# accero_humid_rtc.net
KiCad netlist of a schematic drawn in Altium Designer
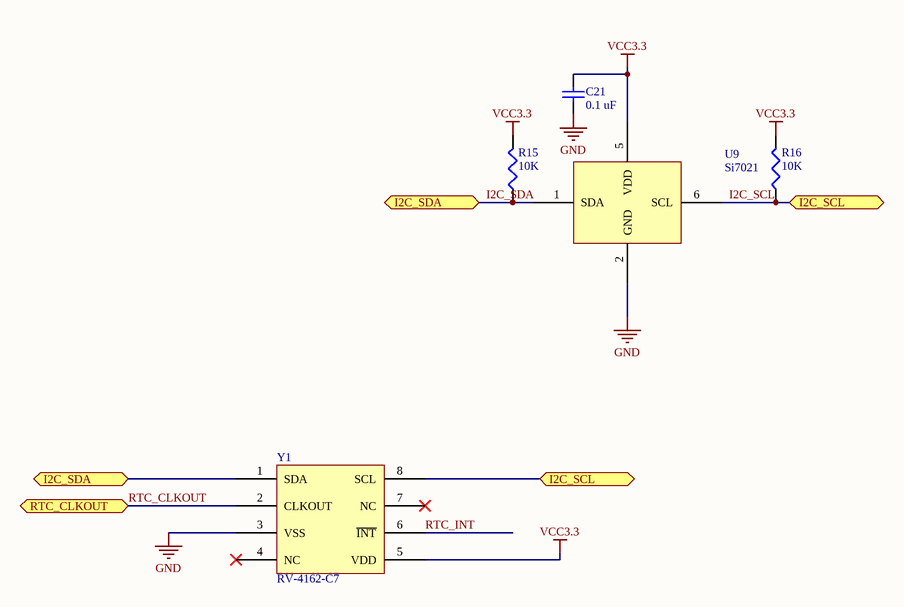
[diagram p0: accero_humid_rtc.SchDoc]

(export (version "E")
  (design (tool "Eeschema 10.0.6"))
  (components
    (comp (ref "C21")
      (value "0.1 uF")
      (footprint "0402")
      (description "Ceramic capacitor, 0.1u, 0402 package")
      (fields (field (name "TOLERANCE") "10%") (field (name "Comment") "Ceramic capacitor"))
      (libsource (lib "rlc") (part "C_0.1u_0402_ceramic"))
    )
    (comp (ref "R15")
      (value "10K")
      (footprint "0402")
      (description "Chip resistor, 10K, 0402 package")
      (fields (field (name "TOLERANCE") "1%") (field (name "POWER") "1/16 W"))
      (libsource (lib "rlc") (part "R_10K_0402"))
    )
    (comp (ref "R16")
      (value "10K")
      (footprint "0402")
      (description "Chip resistor, 10K, 0402 package")
      (fields (field (name "TOLERANCE") "1%") (field (name "POWER") "1/16 W"))
      (libsource (lib "rlc") (part "R_10K_0402"))
    )
    (comp (ref "U9")
      (value "Si7021")
      (footprint "opo_general:DFN6-Si7021")
      (description "Temperature and Humidity Sensor")
      (libsource (lib "opo_general") (part "Si7021"))
    )
    (comp (ref "Y1")
      (value "RV-4162-C7")
      (footprint "RV4162")
      (description "Real Time Clock Module with I2C Bus")
      (libsource (lib "opo_general") (part "RV-4162-C7"))
    )
  )
  (nets
    (net (code "1") (name "/I2C_SCL") (class "Default")
      (node (ref "R16") (pin "2") (pintype "passive"))
      (node (ref "U9") (pin "6") (pinfunction "SCL_6") (pintype "passive"))
      (node (ref "Y1") (pin "8") (pinfunction "SCL_8") (pintype "passive"))
    )
    (net (code "2") (name "/I2C_SDA") (class "Default")
      (node (ref "R15") (pin "2") (pintype "passive"))
      (node (ref "U9") (pin "1") (pinfunction "SDA_1") (pintype "passive"))
      (node (ref "Y1") (pin "1") (pinfunction "SDA_1") (pintype "passive"))
    )
    (net (code "3") (name "/RTC_CLKOUT") (class "Default")
      (node (ref "Y1") (pin "2") (pinfunction "CLKOUT_2") (pintype "passive"))
    )
    (net (code "4") (name "/RTC_INT") (class "Default")
      (node (ref "Y1") (pin "6") (pinfunction "~{INT}_6") (pintype "passive"))
    )
    (net (code "5") (name "GND") (class "Default")
      (node (ref "C21") (pin "2") (pintype "passive"))
      (node (ref "U9") (pin "2") (pinfunction "GND_2") (pintype "passive"))
      (node (ref "Y1") (pin "3") (pinfunction "VSS_3") (pintype "passive"))
    )
    (net (code "6") (name "VCC3.3") (class "Default")
      (node (ref "C21") (pin "1") (pintype "passive"))
      (node (ref "R15") (pin "1") (pintype "passive"))
      (node (ref "R16") (pin "1") (pintype "passive"))
      (node (ref "U9") (pin "5") (pinfunction "VDD_5") (pintype "passive"))
      (node (ref "Y1") (pin "5") (pinfunction "VDD_5") (pintype "passive"))
    )
    (net (code "7") (name "unconnected-(U9-DNC-Pad3)") (class "Default")
      (node (ref "U9") (pin "3") (pinfunction "DNC_3") (pintype "passive"))
    )
    (net (code "8") (name "unconnected-(U9-DNC-Pad4)") (class "Default")
      (node (ref "U9") (pin "4") (pinfunction "DNC_4") (pintype "passive"))
    )
    (net (code "9") (name "unconnected-(U9-DNC-Pad7)") (class "Default")
      (node (ref "U9") (pin "7") (pinfunction "DNC_7") (pintype "passive"))
    )
    (net (code "10") (name "unconnected-(Y1-NC-Pad4)") (class "Default")
      (node (ref "Y1") (pin "4") (pinfunction "NC_4") (pintype "passive+no_connect"))
    )
    (net (code "11") (name "unconnected-(Y1-NC-Pad7)") (class "Default")
      (node (ref "Y1") (pin "7") (pinfunction "NC_7") (pintype "passive+no_connect"))
    )
  )
)
